# Balise_ir_mmetrice.net
KiCad netlist of a schematic drawn in EAGLE
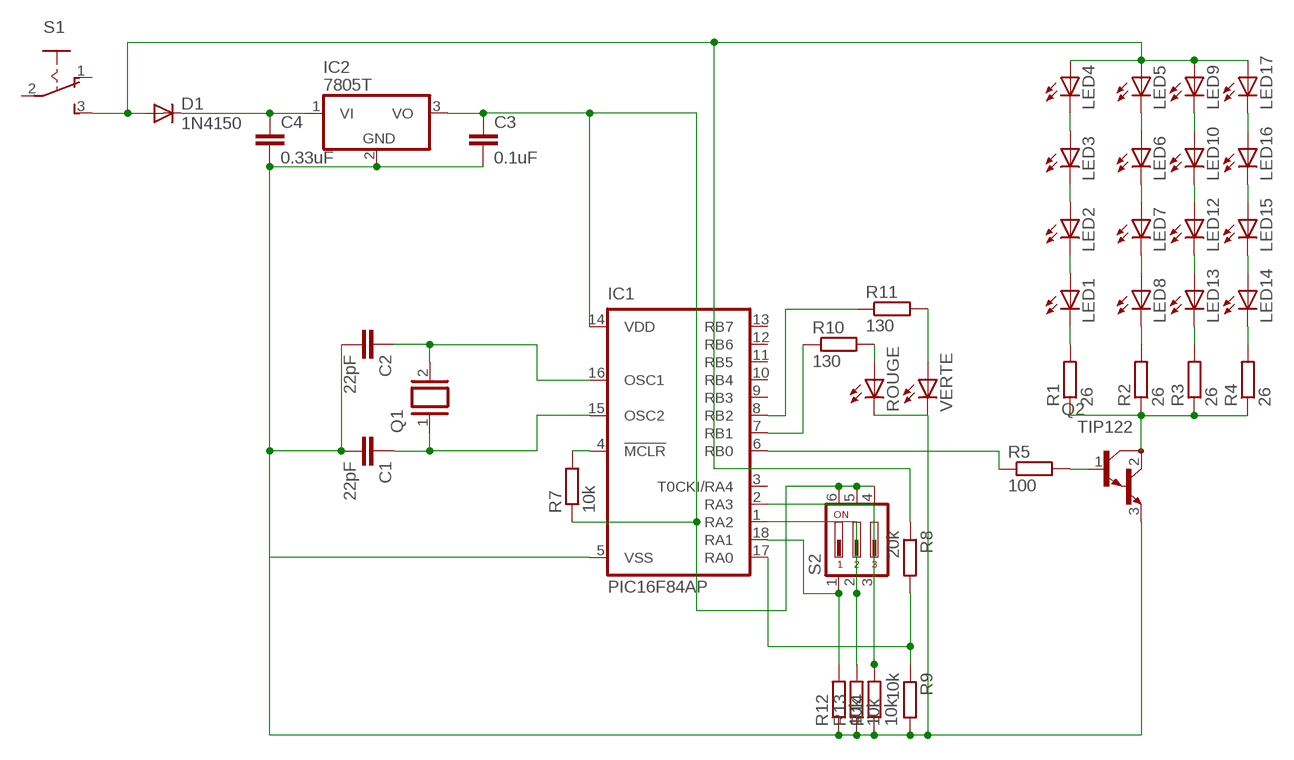
[diagram p0: schematic, sheet 1]

(export (version "E")
  (design (tool "Eeschema 10.0.6"))
  (components
    (comp (ref "C1")
      (value "22pF")
      (footprint "eagle-import:C2.5-4")
      (libsource (lib "eagle-import") (part "C2.5/4"))
    )
    (comp (ref "C2")
      (value "22pF")
      (footprint "eagle-import:C2.5-4")
      (libsource (lib "eagle-import") (part "C2.5/4"))
    )
    (comp (ref "C3")
      (value "0.1uF")
      (footprint "eagle-import:C2.5-4")
      (libsource (lib "eagle-import") (part "C2.5/4"))
    )
    (comp (ref "C4")
      (value "0.33uF")
      (footprint "eagle-import:C2.5-4")
      (libsource (lib "eagle-import") (part "C2.5/4"))
    )
    (comp (ref "D1")
      (value "1N4150")
      (footprint "eagle-import:DO35-7")
      (libsource (lib "eagle-import") (part "1N4148DO35-7"))
    )
    (comp (ref "IC1")
      (value "PIC16F84AP")
      (footprint "eagle-import:DIL18")
      (fields (field (name "MF") "MICROCHIP") (field (name "MPN") "PIC16F84A-04I/P"))
      (libsource (lib "eagle-import") (part "PIC16F8P4A"))
    )
    (comp (ref "IC2")
      (value "7805T")
      (footprint "eagle-import:TO220H")
      (libsource (lib "eagle-import") (part "78T05"))
    )
    (comp (ref "LED1")
      (value "LED3MM")
      (footprint "eagle-import:LED3MM")
      (libsource (lib "eagle-import") (part "LED3MM"))
    )
    (comp (ref "LED2")
      (value "LED3MM")
      (footprint "eagle-import:LED3MM")
      (libsource (lib "eagle-import") (part "LED3MM"))
    )
    (comp (ref "LED3")
      (value "LED3MM")
      (footprint "eagle-import:LED3MM")
      (libsource (lib "eagle-import") (part "LED3MM"))
    )
    (comp (ref "LED4")
      (value "LED3MM")
      (footprint "eagle-import:LED3MM")
      (libsource (lib "eagle-import") (part "LED3MM"))
    )
    (comp (ref "LED5")
      (value "LED3MM")
      (footprint "eagle-import:LED3MM")
      (libsource (lib "eagle-import") (part "LED3MM"))
    )
    (comp (ref "LED6")
      (value "LED3MM")
      (footprint "eagle-import:LED3MM")
      (libsource (lib "eagle-import") (part "LED3MM"))
    )
    (comp (ref "LED7")
      (value "LED3MM")
      (footprint "eagle-import:LED3MM")
      (libsource (lib "eagle-import") (part "LED3MM"))
    )
    (comp (ref "LED8")
      (value "LED3MM")
      (footprint "eagle-import:LED3MM")
      (libsource (lib "eagle-import") (part "LED3MM"))
    )
    (comp (ref "LED9")
      (value "LED3MM")
      (footprint "eagle-import:LED3MM")
      (libsource (lib "eagle-import") (part "LED3MM"))
    )
    (comp (ref "LED10")
      (value "LED3MM")
      (footprint "eagle-import:LED3MM")
      (libsource (lib "eagle-import") (part "LED3MM"))
    )
    (comp (ref "LED12")
      (value "LED3MM")
      (footprint "eagle-import:LED3MM")
      (libsource (lib "eagle-import") (part "LED3MM"))
    )
    (comp (ref "LED13")
      (value "LED3MM")
      (footprint "eagle-import:LED3MM")
      (libsource (lib "eagle-import") (part "LED3MM"))
    )
    (comp (ref "LED14")
      (value "LED3MM")
      (footprint "eagle-import:LED3MM")
      (libsource (lib "eagle-import") (part "LED3MM"))
    )
    (comp (ref "LED15")
      (value "LED3MM")
      (footprint "eagle-import:LED3MM")
      (libsource (lib "eagle-import") (part "LED3MM"))
    )
    (comp (ref "LED16")
      (value "LED3MM")
      (footprint "eagle-import:LED3MM")
      (libsource (lib "eagle-import") (part "LED3MM"))
    )
    (comp (ref "LED17")
      (value "LED3MM")
      (footprint "eagle-import:LED3MM")
      (libsource (lib "eagle-import") (part "LED3MM"))
    )
    (comp (ref "Q1")
      (value "XTAL/S")
      (footprint "eagle-import:QS")
      (libsource (lib "eagle-import") (part "XTAL/S"))
    )
    (comp (ref "Q2")
      (value "TIP122")
      (footprint "eagle-import:TO220")
      (libsource (lib "eagle-import") (part "TIP122"))
    )
    (comp (ref "R1")
      (value "26")
      (footprint "eagle-import:0204_7")
      (libsource (lib "eagle-import") (part "R-EU_0204/7"))
    )
    (comp (ref "R2")
      (value "26")
      (footprint "eagle-import:0204_7")
      (libsource (lib "eagle-import") (part "R-EU_0204/7"))
    )
    (comp (ref "R3")
      (value "26")
      (footprint "eagle-import:0204_7")
      (libsource (lib "eagle-import") (part "R-EU_0204/7"))
    )
    (comp (ref "R4")
      (value "26")
      (footprint "eagle-import:0204_7")
      (libsource (lib "eagle-import") (part "R-EU_0204/7"))
    )
    (comp (ref "R5")
      (value "100")
      (footprint "eagle-import:0204_7")
      (libsource (lib "eagle-import") (part "resistor_R-EU_0204/7"))
    )
    (comp (ref "R7")
      (value "10k")
      (footprint "eagle-import:0207_5V")
      (libsource (lib "eagle-import") (part "R-EU_0207/5V"))
    )
    (comp (ref "R8")
      (value "20k")
      (footprint "eagle-import:0207_5V")
      (libsource (lib "eagle-import") (part "R-EU_0207/5V"))
    )
    (comp (ref "R9")
      (value "10k")
      (footprint "eagle-import:0207_5V")
      (libsource (lib "eagle-import") (part "R-EU_0207/5V"))
    )
    (comp (ref "R10")
      (value "130")
      (footprint "eagle-import:0207_5V")
      (libsource (lib "eagle-import") (part "resistor_R-EU_0207/5V"))
    )
    (comp (ref "R11")
      (value "130")
      (footprint "eagle-import:0207_5V")
      (libsource (lib "eagle-import") (part "resistor_R-EU_0207/5V"))
    )
    (comp (ref "R12")
      (value "10k")
      (footprint "eagle-import:0207_5V")
      (libsource (lib "eagle-import") (part "R-EU_0207/5V"))
    )
    (comp (ref "R13")
      (value "10k")
      (footprint "eagle-import:0207_5V")
      (libsource (lib "eagle-import") (part "R-EU_0207/5V"))
    )
    (comp (ref "R14")
      (value "10k")
      (footprint "eagle-import:0207_5V")
      (libsource (lib "eagle-import") (part "R-EU_0207/5V"))
    )
    (comp (ref "ROUGE")
      (value "LED5MM")
      (footprint "eagle-import:LED5MM")
      (libsource (lib "eagle-import") (part "LED5MM"))
    )
    (comp (ref "S1")
      (value "255SB")
      (footprint "eagle-import:255SB")
      (libsource (lib "eagle-import") (part "255SB"))
    )
    (comp (ref "S2")
      (value "DIP03YL")
      (footprint "eagle-import:DIP03YL")
      (libsource (lib "eagle-import") (part "DIP03YL"))
    )
    (comp (ref "VERTE")
      (value "LED5MM")
      (footprint "eagle-import:LED5MM")
      (libsource (lib "eagle-import") (part "LED5MM"))
    )
  )
  (nets
    (net (code "1") (name "Net-(IC1-OSC1)") (class "Default")
      (node (ref "C2") (pin "1") (pinfunction "1_1") (pintype "passive"))
      (node (ref "IC1") (pin "16") (pinfunction "OSC1_16") (pintype "input"))
      (node (ref "Q1") (pin "2") (pinfunction "2_2") (pintype "passive"))
    )
    (net (code "2") (name "Net-(IC1-OSC2)") (class "Default")
      (node (ref "C1") (pin "1") (pinfunction "1_1") (pintype "passive"))
      (node (ref "IC1") (pin "15") (pinfunction "OSC2_15") (pintype "output"))
      (node (ref "Q1") (pin "1") (pinfunction "1_1") (pintype "passive"))
    )
    (net (code "3") (name "Net-(IC1-RA0)") (class "Default")
      (node (ref "IC1") (pin "17") (pinfunction "RA0_17") (pintype "bidirectional"))
      (node (ref "R8") (pin "2") (pinfunction "2_2") (pintype "passive"))
      (node (ref "R9") (pin "1") (pinfunction "1_1") (pintype "passive"))
    )
    (net (code "4") (name "Net-(IC1-RA1)") (class "Default")
      (node (ref "IC1") (pin "18") (pinfunction "RA1_18") (pintype "bidirectional"))
      (node (ref "R12") (pin "2") (pinfunction "2_2") (pintype "passive"))
      (node (ref "S2") (pin "1") (pinfunction "1_1") (pintype "passive"))
    )
    (net (code "5") (name "Net-(IC1-RA2)") (class "Default")
      (node (ref "IC1") (pin "1") (pinfunction "RA2_1") (pintype "bidirectional"))
      (node (ref "R13") (pin "2") (pinfunction "2_2") (pintype "passive"))
      (node (ref "S2") (pin "2") (pinfunction "2_2") (pintype "passive"))
    )
    (net (code "6") (name "Net-(IC1-RA3)") (class "Default")
      (node (ref "IC1") (pin "2") (pinfunction "RA3_2") (pintype "bidirectional"))
      (node (ref "R14") (pin "2") (pinfunction "2_2") (pintype "passive"))
      (node (ref "S2") (pin "3") (pinfunction "3_3") (pintype "passive"))
    )
    (net (code "7") (name "Net-(IC1-RB0)") (class "Default")
      (node (ref "IC1") (pin "6") (pinfunction "RB0_6") (pintype "bidirectional"))
      (node (ref "R5") (pin "1") (pinfunction "1_1") (pintype "passive"))
    )
    (net (code "8") (name "Net-(IC1-RB1)") (class "Default")
      (node (ref "IC1") (pin "7") (pinfunction "RB1_7") (pintype "bidirectional"))
      (node (ref "R10") (pin "1") (pinfunction "1_1") (pintype "passive"))
    )
    (net (code "9") (name "Net-(IC1-RB2)") (class "Default")
      (node (ref "IC1") (pin "8") (pinfunction "RB2_8") (pintype "bidirectional"))
      (node (ref "R11") (pin "1") (pinfunction "1_1") (pintype "passive"))
    )
    (net (code "10") (name "Net-(IC1-VDD)") (class "Default")
      (node (ref "C3") (pin "1") (pinfunction "1_1") (pintype "passive"))
      (node (ref "IC1") (pin "14") (pinfunction "VDD_14") (pintype "power_in"))
      (node (ref "IC2") (pin "3") (pinfunction "VO_3") (pintype "passive"))
      (node (ref "R7") (pin "1") (pinfunction "1_1") (pintype "passive"))
      (node (ref "S2") (pin "4") (pinfunction "4_4") (pintype "passive"))
      (node (ref "S2") (pin "5") (pinfunction "5_5") (pintype "passive"))
      (node (ref "S2") (pin "6") (pinfunction "6_6") (pintype "passive"))
    )
    (net (code "11") (name "Net-(IC1-VSS)") (class "Default")
      (node (ref "C1") (pin "2") (pinfunction "2_2") (pintype "passive"))
      (node (ref "C2") (pin "2") (pinfunction "2_2") (pintype "passive"))
      (node (ref "C3") (pin "2") (pinfunction "2_2") (pintype "passive"))
      (node (ref "C4") (pin "2") (pinfunction "2_2") (pintype "passive"))
      (node (ref "IC1") (pin "5") (pinfunction "VSS_5") (pintype "power_in"))
      (node (ref "IC2") (pin "2") (pinfunction "GND_2") (pintype "passive"))
      (node (ref "Q2") (pin "3") (pinfunction "E_3") (pintype "passive"))
      (node (ref "R12") (pin "1") (pinfunction "1_1") (pintype "passive"))
      (node (ref "R13") (pin "1") (pinfunction "1_1") (pintype "passive"))
      (node (ref "R14") (pin "1") (pinfunction "1_1") (pintype "passive"))
      (node (ref "R9") (pin "2") (pinfunction "2_2") (pintype "passive"))
      (node (ref "ROUGE") (pin "K") (pinfunction "C_K") (pintype "passive"))
      (node (ref "VERTE") (pin "K") (pinfunction "C_K") (pintype "passive"))
    )
    (net (code "12") (name "Net-(IC1-~{MCLR})") (class "Default")
      (node (ref "IC1") (pin "4") (pinfunction "~{MCLR}_4") (pintype "input"))
      (node (ref "R7") (pin "2") (pinfunction "2_2") (pintype "passive"))
    )
    (net (code "13") (name "Net-(IC2-VI)") (class "Default")
      (node (ref "C4") (pin "1") (pinfunction "1_1") (pintype "passive"))
      (node (ref "D1") (pin "C") (pinfunction "C_C") (pintype "passive"))
      (node (ref "IC2") (pin "1") (pinfunction "VI_1") (pintype "input"))
    )
    (net (code "14") (name "Net-(LED1-C)") (class "Default")
      (node (ref "LED1") (pin "K") (pinfunction "C_K") (pintype "passive"))
      (node (ref "R1") (pin "2") (pinfunction "2_2") (pintype "passive"))
    )
    (net (code "15") (name "Net-(LED2-C)") (class "Default")
      (node (ref "LED1") (pin "A") (pinfunction "A_A") (pintype "passive"))
      (node (ref "LED2") (pin "K") (pinfunction "C_K") (pintype "passive"))
    )
    (net (code "16") (name "Net-(LED3-C)") (class "Default")
      (node (ref "LED2") (pin "A") (pinfunction "A_A") (pintype "passive"))
      (node (ref "LED3") (pin "K") (pinfunction "C_K") (pintype "passive"))
    )
    (net (code "17") (name "Net-(LED4-C)") (class "Default")
      (node (ref "LED3") (pin "A") (pinfunction "A_A") (pintype "passive"))
      (node (ref "LED4") (pin "K") (pinfunction "C_K") (pintype "passive"))
    )
    (net (code "18") (name "Net-(LED5-C)") (class "Default")
      (node (ref "LED5") (pin "K") (pinfunction "C_K") (pintype "passive"))
      (node (ref "LED6") (pin "A") (pinfunction "A_A") (pintype "passive"))
    )
    (net (code "19") (name "Net-(LED6-C)") (class "Default")
      (node (ref "LED6") (pin "K") (pinfunction "C_K") (pintype "passive"))
      (node (ref "LED7") (pin "A") (pinfunction "A_A") (pintype "passive"))
    )
    (net (code "20") (name "Net-(LED7-C)") (class "Default")
      (node (ref "LED7") (pin "K") (pinfunction "C_K") (pintype "passive"))
      (node (ref "LED8") (pin "A") (pinfunction "A_A") (pintype "passive"))
    )
    (net (code "21") (name "Net-(LED8-C)") (class "Default")
      (node (ref "LED8") (pin "K") (pinfunction "C_K") (pintype "passive"))
      (node (ref "R2") (pin "2") (pinfunction "2_2") (pintype "passive"))
    )
    (net (code "22") (name "Net-(LED9-C)") (class "Default")
      (node (ref "LED10") (pin "A") (pinfunction "A_A") (pintype "passive"))
      (node (ref "LED9") (pin "K") (pinfunction "C_K") (pintype "passive"))
    )
    (net (code "23") (name "Net-(LED10-C)") (class "Default")
      (node (ref "LED10") (pin "K") (pinfunction "C_K") (pintype "passive"))
      (node (ref "LED12") (pin "A") (pinfunction "A_A") (pintype "passive"))
    )
    (net (code "24") (name "Net-(LED12-C)") (class "Default")
      (node (ref "LED12") (pin "K") (pinfunction "C_K") (pintype "passive"))
      (node (ref "LED13") (pin "A") (pinfunction "A_A") (pintype "passive"))
    )
    (net (code "25") (name "Net-(LED13-C)") (class "Default")
      (node (ref "LED13") (pin "K") (pinfunction "C_K") (pintype "passive"))
      (node (ref "R3") (pin "2") (pinfunction "2_2") (pintype "passive"))
    )
    (net (code "26") (name "Net-(LED14-C)") (class "Default")
      (node (ref "LED14") (pin "K") (pinfunction "C_K") (pintype "passive"))
      (node (ref "R4") (pin "2") (pinfunction "2_2") (pintype "passive"))
    )
    (net (code "27") (name "Net-(LED15-C)") (class "Default")
      (node (ref "LED14") (pin "A") (pinfunction "A_A") (pintype "passive"))
      (node (ref "LED15") (pin "K") (pinfunction "C_K") (pintype "passive"))
    )
    (net (code "28") (name "Net-(LED16-C)") (class "Default")
      (node (ref "LED15") (pin "A") (pinfunction "A_A") (pintype "passive"))
      (node (ref "LED16") (pin "K") (pinfunction "C_K") (pintype "passive"))
    )
    (net (code "29") (name "Net-(LED17-C)") (class "Default")
      (node (ref "LED16") (pin "A") (pinfunction "A_A") (pintype "passive"))
      (node (ref "LED17") (pin "K") (pinfunction "C_K") (pintype "passive"))
    )
    (net (code "30") (name "Net-(Q2-B)") (class "Default")
      (node (ref "Q2") (pin "1") (pinfunction "B_1") (pintype "passive"))
      (node (ref "R5") (pin "2") (pinfunction "2_2") (pintype "passive"))
    )
    (net (code "31") (name "Net-(Q2-C)") (class "Default")
      (node (ref "Q2") (pin "2") (pinfunction "C_2") (pintype "passive"))
      (node (ref "R1") (pin "1") (pinfunction "1_1") (pintype "passive"))
      (node (ref "R2") (pin "1") (pinfunction "1_1") (pintype "passive"))
      (node (ref "R3") (pin "1") (pinfunction "1_1") (pintype "passive"))
      (node (ref "R4") (pin "1") (pinfunction "1_1") (pintype "passive"))
    )
    (net (code "32") (name "Net-(R10-Pad2)") (class "Default")
      (node (ref "R10") (pin "2") (pinfunction "2_2") (pintype "passive"))
      (node (ref "ROUGE") (pin "A") (pinfunction "A_A") (pintype "passive"))
    )
    (net (code "33") (name "Net-(R11-Pad2)") (class "Default")
      (node (ref "R11") (pin "2") (pinfunction "2_2") (pintype "passive"))
      (node (ref "VERTE") (pin "A") (pinfunction "A_A") (pintype "passive"))
    )
    (net (code "34") (name "Net-(S1-S)") (class "Default")
      (node (ref "D1") (pin "A") (pinfunction "A_A") (pintype "passive"))
      (node (ref "LED17") (pin "A") (pinfunction "A_A") (pintype "passive"))
      (node (ref "LED4") (pin "A") (pinfunction "A_A") (pintype "passive"))
      (node (ref "LED5") (pin "A") (pinfunction "A_A") (pintype "passive"))
      (node (ref "LED9") (pin "A") (pinfunction "A_A") (pintype "passive"))
      (node (ref "R8") (pin "1") (pinfunction "1_1") (pintype "passive"))
      (node (ref "S1") (pin "3") (pinfunction "S_3") (pintype "passive"))
    )
    (net (code "35") (name "unconnected-(IC1-RB3-Pad9)") (class "Default")
      (node (ref "IC1") (pin "9") (pinfunction "RB3_9") (pintype "bidirectional"))
    )
    (net (code "36") (name "unconnected-(IC1-RB4-Pad10)") (class "Default")
      (node (ref "IC1") (pin "10") (pinfunction "RB4_10") (pintype "bidirectional"))
    )
    (net (code "37") (name "unconnected-(IC1-RB5-Pad11)") (class "Default")
      (node (ref "IC1") (pin "11") (pinfunction "RB5_11") (pintype "bidirectional"))
    )
    (net (code "38") (name "unconnected-(IC1-RB6-Pad12)") (class "Default")
      (node (ref "IC1") (pin "12") (pinfunction "RB6_12") (pintype "bidirectional"))
    )
    (net (code "39") (name "unconnected-(IC1-RB7-Pad13)") (class "Default")
      (node (ref "IC1") (pin "13") (pinfunction "RB7_13") (pintype "bidirectional"))
    )
    (net (code "40") (name "unconnected-(IC1-T0CKI{slash}RA4-Pad3)") (class "Default")
      (node (ref "IC1") (pin "3") (pinfunction "T0CKI/RA4_3") (pintype "bidirectional"))
    )
    (net (code "41") (name "unconnected-(S1-O-Pad1)") (class "Default")
      (node (ref "S1") (pin "1") (pinfunction "O_1") (pintype "passive"))
    )
    (net (code "42") (name "unconnected-(S1-P-Pad2)") (class "Default")
      (node (ref "S1") (pin "2") (pinfunction "P_2") (pintype "passive"))
    )
  )
)
